# Switch.net
KiCad netlist of a schematic drawn in Altium Designer
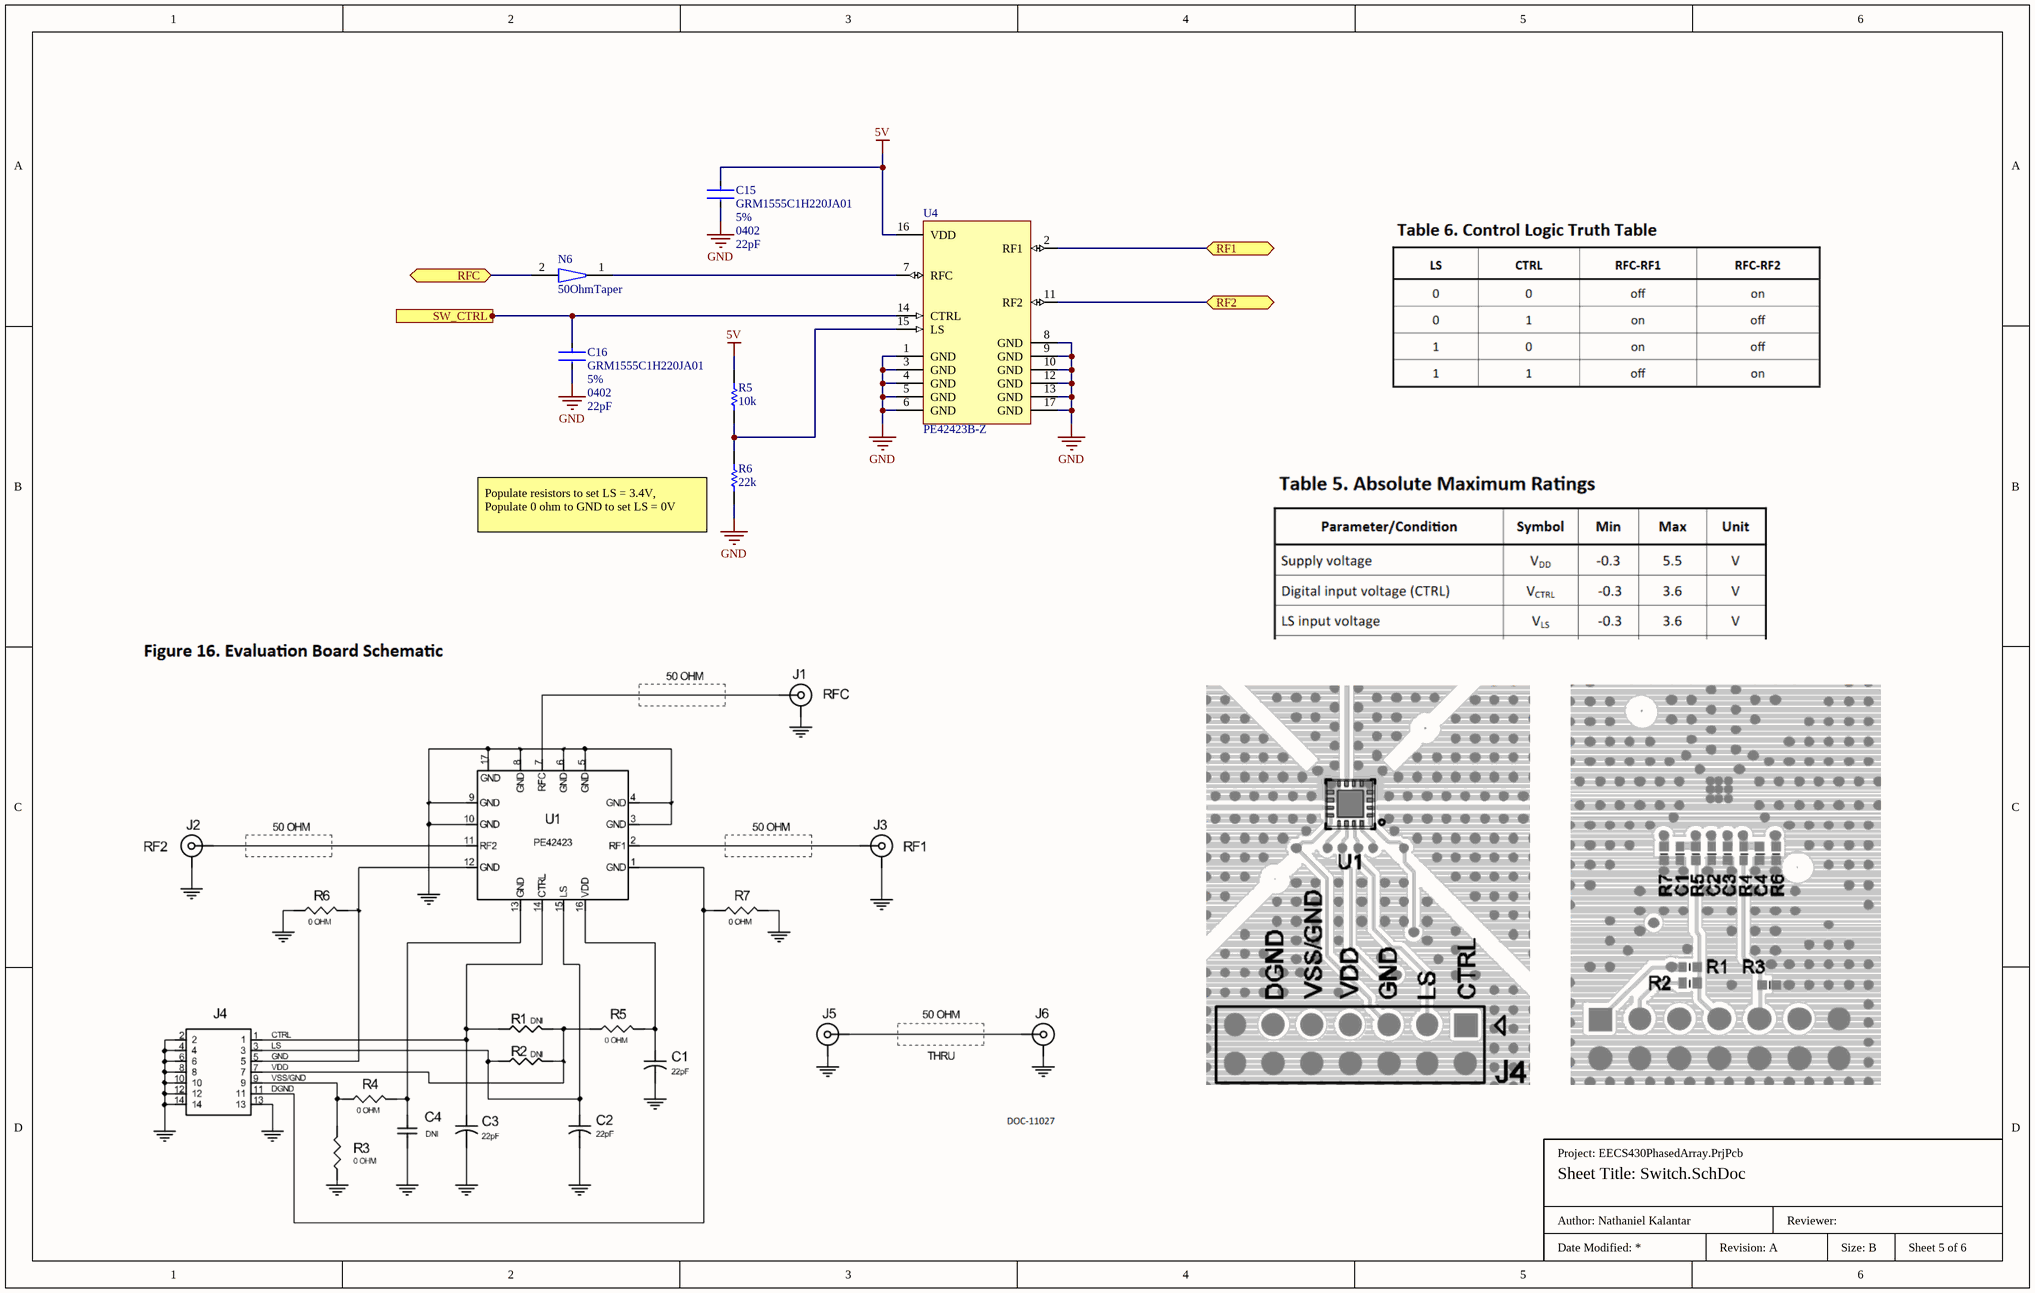
[diagram p0: Switch.SchDoc]

(export (version "E")
  (design (tool "Eeschema 10.0.6"))
  (components
    (comp (ref "C15")
      (value "GRM1555C1H220JA01")
      (footprint "Capacitor0402_Murata")
      (description "22 pF ±5% 50V Ceramic Capacitor C0G, NP0 0402 (1005 Metric)")
      (fields
        (field (name "TOLERANCE") "5%")
        (field (name "PACKAGE") "0402")
        (field (name "ALTIUM_VALUE") "22pF")
      )
      (libsource (lib "EECS430PhasedArray") (part "GRM1555C1H220JA01"))
    )
    (comp (ref "C16")
      (value "GRM1555C1H220JA01")
      (footprint "Capacitor0402_Murata")
      (description "22 pF ±5% 50V Ceramic Capacitor C0G, NP0 0402 (1005 Metric)")
      (fields
        (field (name "TOLERANCE") "5%")
        (field (name "PACKAGE") "0402")
        (field (name "ALTIUM_VALUE") "22pF")
      )
      (libsource (lib "EECS430PhasedArray") (part "GRM1555C1H220JA01"))
    )
    (comp (ref "N6")
      (value "50OhmTaper")
      (footprint "50OhmTaper")
      (description "Triangular taper from 50 Ohms to 0402 width")
      (libsource (lib "EECS430PhasedArray") (part "50OhmTaper"))
    )
    (comp (ref "R5")
      (value "10k")
      (footprint "RESC1608X55X25NL10T15")
      (fields
        (field (name "TOLERANCE") "1%")
        (field (name "MANUFACTURER") "Yageo")
        (field (name "Comment") "RC0603FR-072K2L")
      )
      (libsource (lib "EECS430PhasedArray") (part "Resistor 0603"))
    )
    (comp (ref "R6")
      (value "22k")
      (footprint "RESC1608X55X25NL10T15")
      (fields
        (field (name "TOLERANCE") "1%")
        (field (name "MANUFACTURER") "Yageo")
        (field (name "Comment") "RC0603FR-072K2L")
      )
      (libsource (lib "EECS430PhasedArray") (part "Resistor 0603"))
    )
    (comp (ref "U4")
      (value "PE42423B-Z")
      (footprint "PE42423-QFN127P600-8N")
      (description "RF Switch IC 802.11a/b/g/n/ac SPDT 6 GHz 50Ohm 16-QFN (3x3)")
      (libsource (lib "EECS430PhasedArray") (part "PE42423B-Z"))
    )
  )
  (nets
    (net (code "1") (name "/RF1") (class "Default")
      (node (ref "U4") (pin "2") (pinfunction "RF1_2") (pintype "bidirectional"))
    )
    (net (code "2") (name "/RF2") (class "Default")
      (node (ref "U4") (pin "11") (pinfunction "RF2_11") (pintype "bidirectional"))
    )
    (net (code "3") (name "/RFC") (class "Default")
      (node (ref "N6") (pin "2") (pinfunction "2_2") (pintype "passive"))
    )
    (net (code "4") (name "/SW_CTRL") (class "Default")
      (node (ref "C16") (pin "1") (pinfunction "1_1") (pintype "passive"))
      (node (ref "U4") (pin "14") (pinfunction "CTRL_14") (pintype "input"))
    )
    (net (code "5") (name "5V") (class "Default")
      (node (ref "C15") (pin "1") (pinfunction "1_1") (pintype "passive"))
      (node (ref "R5") (pin "2") (pinfunction "2_2") (pintype "passive"))
      (node (ref "U4") (pin "16") (pinfunction "VDD_16") (pintype "power_in"))
    )
    (net (code "6") (name "GND") (class "Default")
      (node (ref "C15") (pin "2") (pinfunction "2_2") (pintype "passive"))
      (node (ref "C16") (pin "2") (pinfunction "2_2") (pintype "passive"))
      (node (ref "R6") (pin "1") (pinfunction "1_1") (pintype "passive"))
      (node (ref "U4") (pin "1") (pinfunction "GND_1") (pintype "power_in"))
      (node (ref "U4") (pin "10") (pinfunction "GND_10") (pintype "power_in"))
      (node (ref "U4") (pin "12") (pinfunction "GND_12") (pintype "power_in"))
      (node (ref "U4") (pin "13") (pinfunction "GND_13") (pintype "power_in"))
      (node (ref "U4") (pin "17") (pinfunction "GND_17") (pintype "power_in"))
      (node (ref "U4") (pin "3") (pinfunction "GND_3") (pintype "power_in"))
      (node (ref "U4") (pin "4") (pinfunction "GND_4") (pintype "power_in"))
      (node (ref "U4") (pin "5") (pinfunction "GND_5") (pintype "power_in"))
      (node (ref "U4") (pin "6") (pinfunction "GND_6") (pintype "power_in"))
      (node (ref "U4") (pin "8") (pinfunction "GND_8") (pintype "power_in"))
      (node (ref "U4") (pin "9") (pinfunction "GND_9") (pintype "power_in"))
    )
    (net (code "7") (name "Net-(U4-LS)") (class "Default")
      (node (ref "R5") (pin "1") (pinfunction "1_1") (pintype "passive"))
      (node (ref "R6") (pin "2") (pinfunction "2_2") (pintype "passive"))
      (node (ref "U4") (pin "15") (pinfunction "LS_15") (pintype "input"))
    )
    (net (code "8") (name "Net-(U4-RFC)") (class "Default")
      (node (ref "N6") (pin "1") (pinfunction "1_1") (pintype "passive"))
      (node (ref "U4") (pin "7") (pinfunction "RFC_7") (pintype "bidirectional"))
    )
  )
)
